# I2C_bus_components.net
KiCad netlist of a schematic drawn in Altium Designer
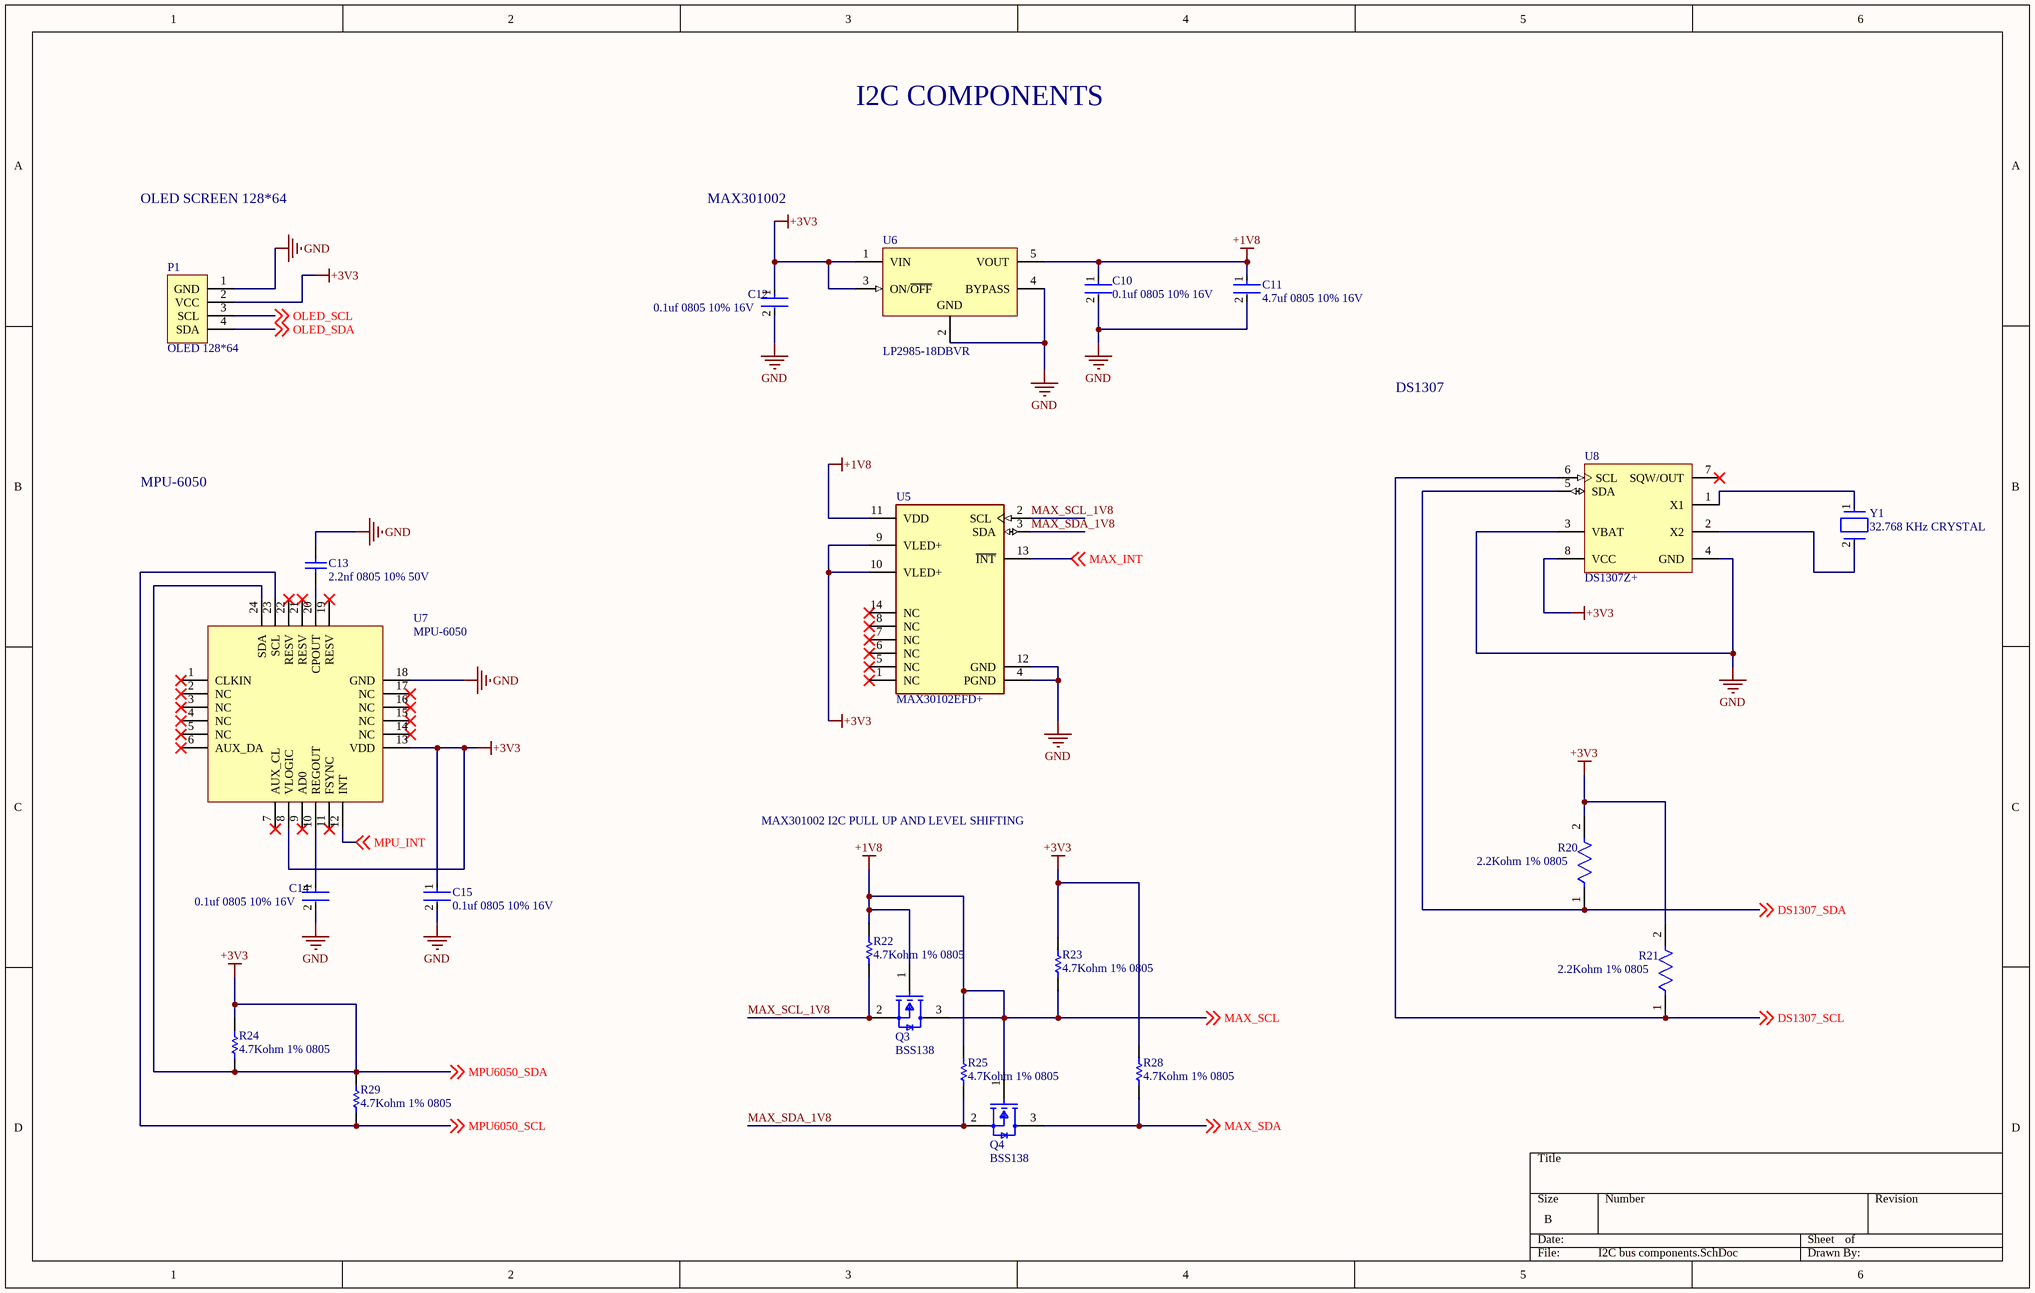
[diagram p0: I2C bus components.SchDoc]

(export (version "E")
  (design (tool "Eeschema 10.0.6"))
  (components
    (comp (ref "C10")
      (value "0.1uf 0805 10% 16V")
      (footprint "FP-CC0805-0_85-MFG")
      (description "CAP CER 0.1UF 16V X7R 0805")
      (fields
        (field (name "MANUFACTURER PART NUMBER") "CC0805KRX7R7BB104")
        (field (name "MANUFACTURER") "Yageo")
      )
      (libsource (lib "Altium Content Vault") (part "11868f565c42a9108669ba33697ecf6"))
    )
    (comp (ref "C11")
      (value "4.7uf 0805 10% 16V")
      (footprint "FP-CGA4J-IPC_A")
      (description "Cap Ceramic 4.7uF 16V X7R 10% Pad SMD 0805 +125°C Automotive T/R")
      (fields (field (name "TOLERANCE") "10%"))
      (libsource (lib "Altium Content Vault") (part "b4654b650e69147ec39a6b967a45e02"))
    )
    (comp (ref "C12")
      (value "0.1uf 0805 10% 16V")
      (footprint "FP-CC0805-0_85-MFG")
      (description "CAP CER 0.1UF 16V X7R 0805")
      (fields
        (field (name "MANUFACTURER PART NUMBER") "CC0805KRX7R7BB104")
        (field (name "MANUFACTURER") "Yageo")
      )
      (libsource (lib "Altium Content Vault") (part "11868f565c42a9108669ba33697ecf6"))
    )
    (comp (ref "C13")
      (value "2.2nf 0805 10% 50V")
      (footprint "CAPC2013X135X50NL15T20")
      (fields (field (name "MANUFACTURER") "Vitramon") (field (name "PART NUMBER") "VJ0805Y222KXACW1BC"))
      (libsource (lib "Altium Content Vault") (part "CAP"))
    )
    (comp (ref "C14")
      (value "0.1uf 0805 10% 16V")
      (footprint "FP-CC0805-0_85-MFG")
      (description "CAP CER 0.1UF 16V X7R 0805")
      (fields
        (field (name "MANUFACTURER PART NUMBER") "CC0805KRX7R7BB104")
        (field (name "MANUFACTURER") "Yageo")
      )
      (libsource (lib "Altium Content Vault") (part "11868f565c42a9108669ba33697ecf6"))
    )
    (comp (ref "C15")
      (value "0.1uf 0805 10% 16V")
      (footprint "FP-CC0805-0_85-MFG")
      (description "CAP CER 0.1UF 16V X7R 0805")
      (fields
        (field (name "MANUFACTURER PART NUMBER") "CC0805KRX7R7BB104")
        (field (name "MANUFACTURER") "Yageo")
      )
      (libsource (lib "Altium Content Vault") (part "11868f565c42a9108669ba33697ecf6"))
    )
    (comp (ref "P1")
      (value "OLED 128*64")
      (footprint "4pins smd")
      (libsource (lib "Schlib1") (part "OLED 128*64"))
    )
    (comp (ref "Q3")
      (value "BSS138")
      (footprint "FP-318-08-IPC_B")
      (description "MOSFET N-CH 50V 220MA SOT-23")
      (libsource (lib "Altium Content Vault") (part "3b9c635fedb024a5347a57b145af9cc"))
    )
    (comp (ref "Q4")
      (value "BSS138")
      (footprint "FP-318-08-IPC_B")
      (description "MOSFET N-CH 50V 220MA SOT-23")
      (libsource (lib "Altium Content Vault") (part "3b9c635fedb024a5347a57b145af9cc"))
    )
    (comp (ref "R20")
      (value "2.2Kohm 1% 0805")
      (footprint "FP-RT0805-MFG")
      (description "RES SMD 2.2K OHM 1% 1/8W 0805")
      (fields
        (field (name "TOLERANCE") "0.0001")
        (field (name "OCTOPART") "https://octopart.com/rt0805fre072k2l-yageo-42273028")
      )
      (libsource (lib "Altium Content Vault") (part "1029c3af85768c4190bb7ad29bc67b5"))
    )
    (comp (ref "R21")
      (value "2.2Kohm 1% 0805")
      (footprint "FP-RT0805-MFG")
      (description "RES SMD 2.2K OHM 1% 1/8W 0805")
      (fields
        (field (name "TOLERANCE") "0.0001")
        (field (name "OCTOPART") "https://octopart.com/rt0805fre072k2l-yageo-42273028")
      )
      (libsource (lib "Altium Content Vault") (part "1029c3af85768c4190bb7ad29bc67b5"))
    )
    (comp (ref "R22")
      (value "4.7Kohm 1% 0805")
      (footprint "RESC0805(2012)_M")
      (description "4K7 0.125W 1% 0805 (2012 Metric)  SMD")
      (fields (field (name "POWER") "0.125 W") (field (name "TOLERANCE") "1 %"))
      (libsource (lib "Altium Content Vault") (part "RES"))
    )
    (comp (ref "R23")
      (value "4.7Kohm 1% 0805")
      (footprint "RESC0805(2012)_M")
      (description "4K7 0.125W 1% 0805 (2012 Metric)  SMD")
      (fields (field (name "POWER") "0.125 W") (field (name "TOLERANCE") "1 %"))
      (libsource (lib "Altium Content Vault") (part "RES"))
    )
    (comp (ref "R24")
      (value "4.7Kohm 1% 0805")
      (footprint "RESC0805(2012)_M")
      (description "4K7 0.125W 1% 0805 (2012 Metric)  SMD")
      (fields (field (name "POWER") "0.125 W") (field (name "TOLERANCE") "1 %"))
      (libsource (lib "Altium Content Vault") (part "RES"))
    )
    (comp (ref "R25")
      (value "4.7Kohm 1% 0805")
      (footprint "RESC0805(2012)_M")
      (description "4K7 0.125W 1% 0805 (2012 Metric)  SMD")
      (fields (field (name "POWER") "0.125 W") (field (name "TOLERANCE") "1 %"))
      (libsource (lib "Altium Content Vault") (part "RES"))
    )
    (comp (ref "R28")
      (value "4.7Kohm 1% 0805")
      (footprint "RESC0805(2012)_M")
      (description "4K7 0.125W 1% 0805 (2012 Metric)  SMD")
      (fields (field (name "POWER") "0.125 W") (field (name "TOLERANCE") "1 %"))
      (libsource (lib "Altium Content Vault") (part "RES"))
    )
    (comp (ref "R29")
      (value "4.7Kohm 1% 0805")
      (footprint "RESC0805(2012)_M")
      (description "4K7 0.125W 1% 0805 (2012 Metric)  SMD")
      (fields (field (name "POWER") "0.125 W") (field (name "TOLERANCE") "1 %"))
      (libsource (lib "Altium Content Vault") (part "RES"))
    )
    (comp (ref "U5")
      (value "MAX30102EFD+")
      (footprint "MAX30102")
      (description "IC SENSOR OXIMETER/HEARTRATE")
      (fields (field (name "MANUFACTURER") "Maxim"))
      (libsource (lib "Schlib1") (part "MAX30102EFD+"))
    )
    (comp (ref "U6")
      (value "LP2985-18DBVR")
      (footprint "DBV0005A_M")
      (fields (field (name "MANUFACTURER") "Texas Instruments"))
      (libsource (lib "Altium Content Vault") (part "TI-LP2985_A-10DBV5"))
    )
    (comp (ref "U7")
      (value "MPU-6050")
      (footprint "MPU-6050")
      (description "INVENSENSE   MPU-6050   GYRO / ACCEL, 6-AXIS, I2C, QFN-24")
      (fields (field (name "MANUFACTURER") "TDK InvenSense"))
      (libsource (lib "Schlib1") (part "MPU-6050"))
    )
    (comp (ref "U8")
      (value "DS1307Z+")
      (footprint "S8+2_L")
      (description "64 x 8, Serial, I2C Real-Time Clock, 5.0V, 8-Pin SO, 0 to 70 degC, Pb-Free")
      (libsource (lib "Altium Content Vault") (part "PR_RTC_DS1307-IL8"))
    )
    (comp (ref "Y1")
      (value "32.768 KHz CRYSTAL")
      (footprint "FP-ECX-34Q-MFG")
      (description "CRYSTAL 32.768KHZ 12.5PF SMD")
      (libsource (lib "Altium Content Vault") (part "99724985039315a44fd0d1401b84e49"))
    )
  )
  (nets
    (net (code "1") (name "+1V8") (class "Default")
      (node (ref "C10") (pin "1") (pinfunction "1_1") (pintype "passive"))
      (node (ref "C11") (pin "1") (pinfunction "1_1") (pintype "passive"))
      (node (ref "Q3") (pin "1") (pinfunction "G_1") (pintype "passive"))
      (node (ref "Q3") (pin "3") (pinfunction "D_3") (pintype "passive"))
      (node (ref "Q4") (pin "1") (pinfunction "G_1") (pintype "passive"))
      (node (ref "R22") (pin "2") (pinfunction "2_2") (pintype "passive"))
      (node (ref "R23") (pin "1") (pinfunction "1_1") (pintype "passive"))
      (node (ref "R25") (pin "2") (pinfunction "2_2") (pintype "passive"))
      (node (ref "U5") (pin "11") (pinfunction "VDD_11") (pintype "power_in"))
      (node (ref "U6") (pin "5") (pinfunction "VOUT_5") (pintype "power_in"))
    )
    (net (code "2") (name "+3V3") (class "Default")
      (node (ref "C12") (pin "1") (pinfunction "1_1") (pintype "passive"))
      (node (ref "C15") (pin "1") (pinfunction "1_1") (pintype "passive"))
      (node (ref "P1") (pin "2") (pinfunction "VCC_2") (pintype "passive"))
      (node (ref "R20") (pin "2") (pinfunction "2_2") (pintype "passive"))
      (node (ref "R21") (pin "2") (pinfunction "2_2") (pintype "passive"))
      (node (ref "R23") (pin "2") (pinfunction "2_2") (pintype "passive"))
      (node (ref "R24") (pin "1") (pinfunction "1_1") (pintype "passive"))
      (node (ref "R24") (pin "2") (pinfunction "2_2") (pintype "passive"))
      (node (ref "R28") (pin "2") (pinfunction "2_2") (pintype "passive"))
      (node (ref "R29") (pin "2") (pinfunction "2_2") (pintype "passive"))
      (node (ref "U5") (pin "10") (pinfunction "VLED+_10") (pintype "power_in"))
      (node (ref "U5") (pin "9") (pinfunction "VLED+_9") (pintype "power_in"))
      (node (ref "U6") (pin "1") (pinfunction "VIN_1") (pintype "power_in"))
      (node (ref "U6") (pin "3") (pinfunction "ON/~{OFF}_3") (pintype "input"))
      (node (ref "U7") (pin "13") (pinfunction "VDD_13") (pintype "passive"))
      (node (ref "U7") (pin "24") (pinfunction "SDA_24") (pintype "passive"))
      (node (ref "U7") (pin "8") (pinfunction "VLOGIC_8") (pintype "passive"))
      (node (ref "U8") (pin "8") (pinfunction "VCC_8") (pintype "power_in"))
    )
    (net (code "3") (name "/MAX_SCL_1V8") (class "Default")
      (node (ref "Q3") (pin "2") (pinfunction "S_2") (pintype "passive"))
      (node (ref "R22") (pin "1") (pinfunction "1_1") (pintype "passive"))
      (node (ref "U5") (pin "2") (pinfunction "SCL_2") (pintype "input"))
    )
    (net (code "4") (name "/MAX_SDA_1V8") (class "Default")
      (node (ref "Q4") (pin "2") (pinfunction "S_2") (pintype "passive"))
      (node (ref "R25") (pin "1") (pinfunction "1_1") (pintype "passive"))
      (node (ref "U5") (pin "3") (pinfunction "SDA_3") (pintype "bidirectional"))
    )
    (net (code "5") (name "DS1307_SCL") (class "Default")
      (node (ref "R21") (pin "1") (pinfunction "1_1") (pintype "passive"))
      (node (ref "U8") (pin "6") (pinfunction "SCL_6") (pintype "input"))
    )
    (net (code "6") (name "DS1307_SDA") (class "Default")
      (node (ref "R20") (pin "1") (pinfunction "1_1") (pintype "passive"))
      (node (ref "U8") (pin "5") (pinfunction "SDA_5") (pintype "bidirectional"))
    )
    (net (code "7") (name "GND") (class "Default")
      (node (ref "C10") (pin "2") (pinfunction "2_2") (pintype "passive"))
      (node (ref "C11") (pin "2") (pinfunction "2_2") (pintype "passive"))
      (node (ref "C12") (pin "2") (pinfunction "2_2") (pintype "passive"))
      (node (ref "C13") (pin "2") (pinfunction "2_2") (pintype "passive"))
      (node (ref "C14") (pin "2") (pinfunction "2_2") (pintype "passive"))
      (node (ref "C15") (pin "2") (pinfunction "2_2") (pintype "passive"))
      (node (ref "P1") (pin "1") (pinfunction "GND_1") (pintype "passive"))
      (node (ref "U5") (pin "12") (pinfunction "GND_12") (pintype "power_in"))
      (node (ref "U5") (pin "4") (pinfunction "PGND_4") (pintype "power_in"))
      (node (ref "U6") (pin "2") (pinfunction "GND_2") (pintype "power_in"))
      (node (ref "U6") (pin "4") (pinfunction "BYPASS_4") (pintype "passive"))
      (node (ref "U7") (pin "18") (pinfunction "GND_18") (pintype "passive"))
      (node (ref "U8") (pin "3") (pinfunction "VBAT_3") (pintype "power_in"))
      (node (ref "U8") (pin "4") (pinfunction "GND_4") (pintype "power_in"))
    )
    (net (code "8") (name "MAX_INT") (class "Default")
      (node (ref "U5") (pin "13") (pinfunction "~{INT}_13") (pintype "open_collector"))
    )
    (net (code "9") (name "MAX_SDA") (class "Default")
      (node (ref "Q4") (pin "3") (pinfunction "D_3") (pintype "passive"))
      (node (ref "R28") (pin "1") (pinfunction "1_1") (pintype "passive"))
    )
    (net (code "10") (name "MPU6050_SCL") (class "Default")
      (node (ref "R29") (pin "1") (pinfunction "1_1") (pintype "passive"))
      (node (ref "U7") (pin "23") (pinfunction "SCL_23") (pintype "passive"))
    )
    (net (code "11") (name "MPU_INT") (class "Default")
      (node (ref "U7") (pin "12") (pinfunction "INT_12") (pintype "passive"))
    )
    (net (code "12") (name "Net-(U7-CPOUT)") (class "Default")
      (node (ref "C13") (pin "1") (pinfunction "1_1") (pintype "passive"))
      (node (ref "U7") (pin "20") (pinfunction "CPOUT_20") (pintype "passive"))
    )
    (net (code "13") (name "Net-(U7-REGOUT)") (class "Default")
      (node (ref "C14") (pin "1") (pinfunction "1_1") (pintype "passive"))
      (node (ref "U7") (pin "10") (pinfunction "REGOUT_10") (pintype "passive"))
    )
    (net (code "14") (name "Net-(U8-X1)") (class "Default")
      (node (ref "U8") (pin "1") (pinfunction "X1_1") (pintype "passive"))
      (node (ref "Y1") (pin "1") (pinfunction "In/Out_1") (pintype "bidirectional"))
    )
    (net (code "15") (name "Net-(U8-X2)") (class "Default")
      (node (ref "U8") (pin "2") (pinfunction "X2_2") (pintype "passive"))
      (node (ref "Y1") (pin "2") (pinfunction "Out/In_2") (pintype "bidirectional"))
    )
    (net (code "16") (name "OLED_SCL") (class "Default")
      (node (ref "P1") (pin "3") (pinfunction "SCL_3") (pintype "passive"))
    )
    (net (code "17") (name "OLED_SDA") (class "Default")
      (node (ref "P1") (pin "4") (pinfunction "SDA_4") (pintype "passive"))
    )
    (net (code "18") (name "unconnected-(U5-NC-Pad1)") (class "Default")
      (node (ref "U5") (pin "1") (pinfunction "NC_1") (pintype "passive+no_connect"))
    )
    (net (code "19") (name "unconnected-(U5-NC-Pad5)") (class "Default")
      (node (ref "U5") (pin "5") (pinfunction "NC_5") (pintype "passive+no_connect"))
    )
    (net (code "20") (name "unconnected-(U5-NC-Pad6)") (class "Default")
      (node (ref "U5") (pin "6") (pinfunction "NC_6") (pintype "passive+no_connect"))
    )
    (net (code "21") (name "unconnected-(U5-NC-Pad7)") (class "Default")
      (node (ref "U5") (pin "7") (pinfunction "NC_7") (pintype "passive+no_connect"))
    )
    (net (code "22") (name "unconnected-(U5-NC-Pad8)") (class "Default")
      (node (ref "U5") (pin "8") (pinfunction "NC_8") (pintype "passive+no_connect"))
    )
    (net (code "23") (name "unconnected-(U5-NC-Pad14)") (class "Default")
      (node (ref "U5") (pin "14") (pinfunction "NC_14") (pintype "passive+no_connect"))
    )
    (net (code "24") (name "unconnected-(U7-AD0-Pad9)") (class "Default")
      (node (ref "U7") (pin "9") (pinfunction "AD0_9") (pintype "passive+no_connect"))
    )
    (net (code "25") (name "unconnected-(U7-AUX_CL-Pad7)") (class "Default")
      (node (ref "U7") (pin "7") (pinfunction "AUX_CL_7") (pintype "passive+no_connect"))
    )
    (net (code "26") (name "unconnected-(U7-AUX_DA-Pad6)") (class "Default")
      (node (ref "U7") (pin "6") (pinfunction "AUX_DA_6") (pintype "passive+no_connect"))
    )
    (net (code "27") (name "unconnected-(U7-CLKIN-Pad1)") (class "Default")
      (node (ref "U7") (pin "1") (pinfunction "CLKIN_1") (pintype "passive+no_connect"))
    )
    (net (code "28") (name "unconnected-(U7-FSYNC-Pad11)") (class "Default")
      (node (ref "U7") (pin "11") (pinfunction "FSYNC_11") (pintype "passive+no_connect"))
    )
    (net (code "29") (name "unconnected-(U7-NC-Pad2)") (class "Default")
      (node (ref "U7") (pin "2") (pinfunction "NC_2") (pintype "passive+no_connect"))
    )
    (net (code "30") (name "unconnected-(U7-NC-Pad3)") (class "Default")
      (node (ref "U7") (pin "3") (pinfunction "NC_3") (pintype "passive+no_connect"))
    )
    (net (code "31") (name "unconnected-(U7-NC-Pad4)") (class "Default")
      (node (ref "U7") (pin "4") (pinfunction "NC_4") (pintype "passive+no_connect"))
    )
    (net (code "32") (name "unconnected-(U7-NC-Pad5)") (class "Default")
      (node (ref "U7") (pin "5") (pinfunction "NC_5") (pintype "passive+no_connect"))
    )
    (net (code "33") (name "unconnected-(U7-NC-Pad14)") (class "Default")
      (node (ref "U7") (pin "14") (pinfunction "NC_14") (pintype "passive+no_connect"))
    )
    (net (code "34") (name "unconnected-(U7-NC-Pad15)") (class "Default")
      (node (ref "U7") (pin "15") (pinfunction "NC_15") (pintype "passive+no_connect"))
    )
    (net (code "35") (name "unconnected-(U7-NC-Pad16)") (class "Default")
      (node (ref "U7") (pin "16") (pinfunction "NC_16") (pintype "passive+no_connect"))
    )
    (net (code "36") (name "unconnected-(U7-NC-Pad17)") (class "Default")
      (node (ref "U7") (pin "17") (pinfunction "NC_17") (pintype "passive+no_connect"))
    )
    (net (code "37") (name "unconnected-(U7-RESV-Pad19)") (class "Default")
      (node (ref "U7") (pin "19") (pinfunction "RESV_19") (pintype "passive+no_connect"))
    )
    (net (code "38") (name "unconnected-(U7-RESV-Pad21)") (class "Default")
      (node (ref "U7") (pin "21") (pinfunction "RESV_21") (pintype "passive+no_connect"))
    )
    (net (code "39") (name "unconnected-(U7-RESV-Pad22)") (class "Default")
      (node (ref "U7") (pin "22") (pinfunction "RESV_22") (pintype "passive+no_connect"))
    )
    (net (code "40") (name "unconnected-(U8-SQW{slash}OUT-Pad7)") (class "Default")
      (node (ref "U8") (pin "7") (pinfunction "SQW/OUT_7") (pintype "open_collector+no_connect"))
    )
  )
)
